# MCH_FPGA_Bank_0_CFG.net
KiCad netlist of a schematic drawn in Altium Designer
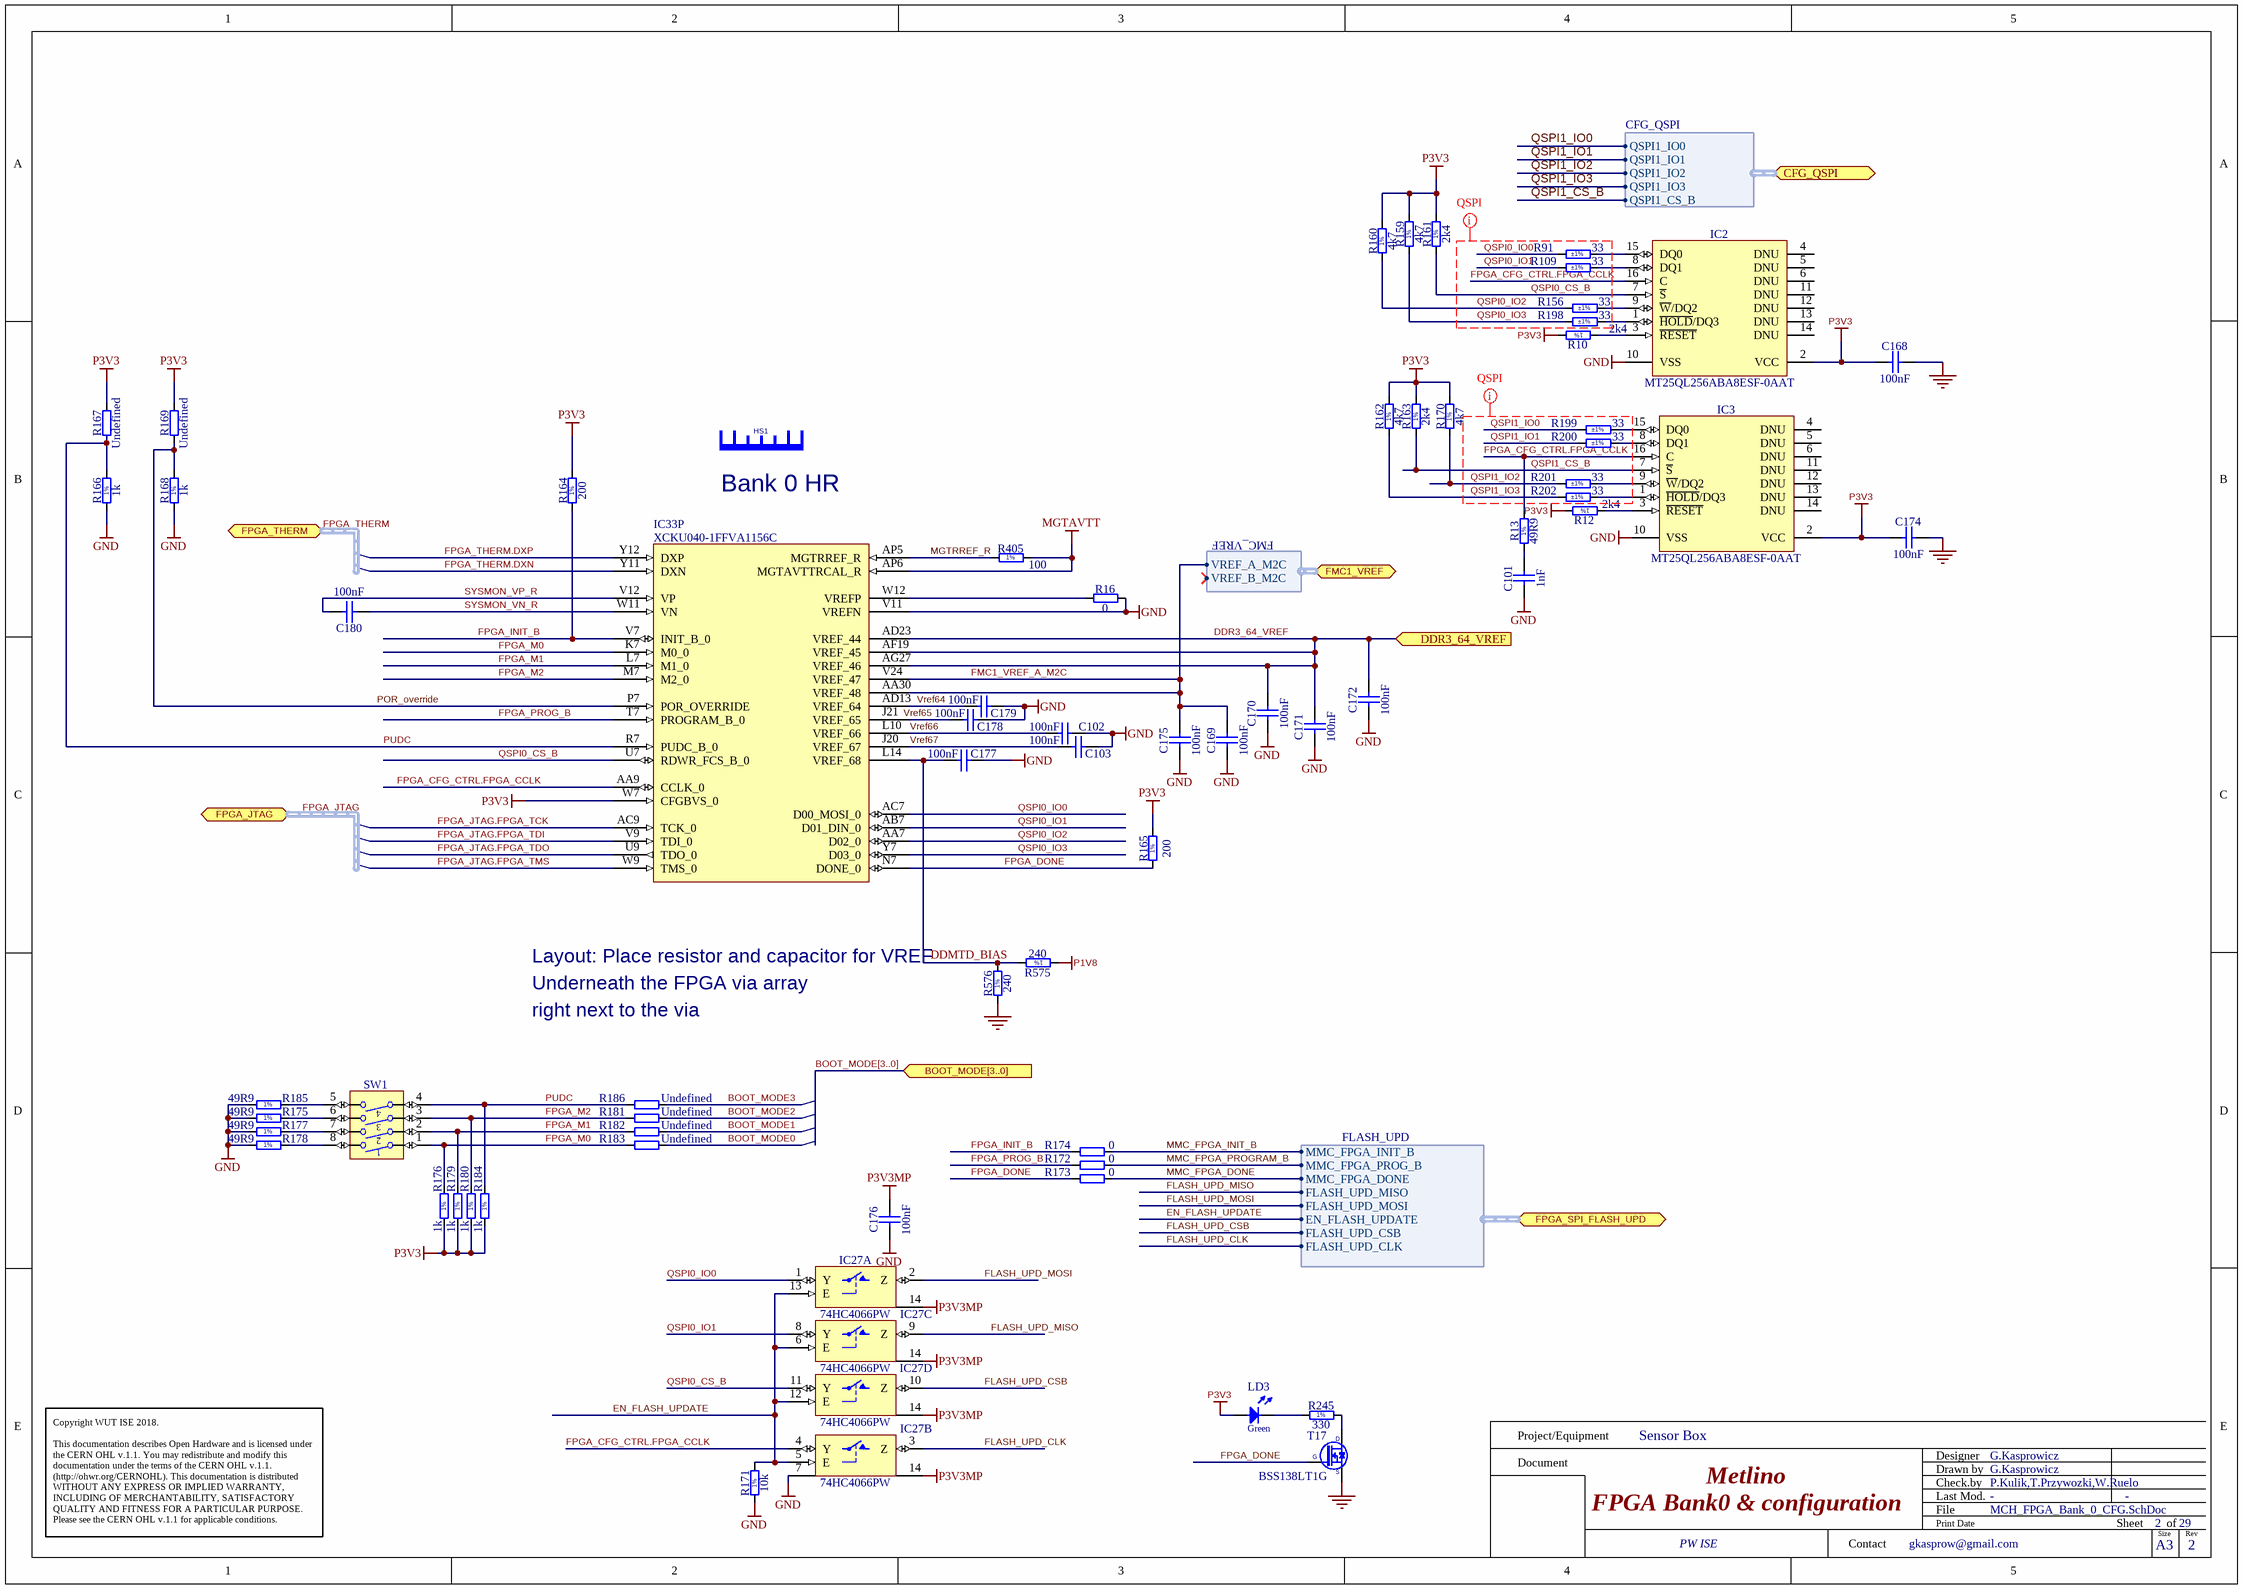
[diagram p0: MCH_FPGA_Bank_0_CFG.SchDoc]

(export (version "E")
  (design (tool "Eeschema 10.0.6"))
  (components
    (comp (ref "C101")
      (value "1nF")
      (footprint "CAPC1005X55N")
      (description "Non-polarised capacitor")
      (fields
        (field (name "MANUFACTURER PART NUMBER") "CC0402_1NF_50V_10%_X7R")
        (field (name "MANUFACTURER") "GENERIC")
        (field (name "AUTHOR") "CERN DEM JLC")
      )
      (libsource (lib "Capacitors") (part "Capacitor - non polarized"))
    )
    (comp (ref "C102")
      (value "100nF")
      (footprint "CAPC0603X33N")
      (description "Non-polarised capacitor")
      (fields
        (field (name "MANUFACTURER PART NUMBER") "CC0201_100NF_6.3V_10%_X5R")
        (field (name "MANUFACTURER") "GENERIC")
        (field (name "AUTHOR") "CERN DEM JLC")
      )
      (libsource (lib "Capacitors") (part "Capacitor - non polarized"))
    )
    (comp (ref "C103")
      (value "100nF")
      (footprint "CAPC0603X33N")
      (description "Non-polarised capacitor")
      (fields
        (field (name "MANUFACTURER PART NUMBER") "CC0201_100NF_6.3V_10%_X5R")
        (field (name "MANUFACTURER") "GENERIC")
        (field (name "AUTHOR") "CERN DEM JLC")
      )
      (libsource (lib "Capacitors") (part "Capacitor - non polarized"))
    )
    (comp (ref "C168")
      (value "100nF")
      (footprint "CAPC0603X33N")
      (description "Non-polarised capacitor")
      (fields
        (field (name "MANUFACTURER PART NUMBER") "CC0201_100NF_6.3V_10%_X5R")
        (field (name "MANUFACTURER") "GENERIC")
        (field (name "AUTHOR") "CERN DEM JLC")
      )
      (libsource (lib "Capacitors") (part "Capacitor - non polarized"))
    )
    (comp (ref "C169")
      (value "100nF")
      (footprint "CAPC0603X33N")
      (description "Non-polarised capacitor")
      (fields
        (field (name "MANUFACTURER PART NUMBER") "CC0201_100NF_6.3V_10%_X5R")
        (field (name "MANUFACTURER") "GENERIC")
        (field (name "AUTHOR") "CERN DEM JLC")
      )
      (libsource (lib "Capacitors") (part "Capacitor - non polarized"))
    )
    (comp (ref "C170")
      (value "100nF")
      (footprint "CAPC0603X33N")
      (description "Non-polarised capacitor")
      (fields
        (field (name "MANUFACTURER PART NUMBER") "CC0201_100NF_6.3V_10%_X5R")
        (field (name "MANUFACTURER") "GENERIC")
        (field (name "AUTHOR") "CERN DEM JLC")
      )
      (libsource (lib "Capacitors") (part "Capacitor - non polarized"))
    )
    (comp (ref "C171")
      (value "100nF")
      (footprint "CAPC0603X33N")
      (description "Non-polarised capacitor")
      (fields
        (field (name "MANUFACTURER PART NUMBER") "CC0201_100NF_6.3V_10%_X5R")
        (field (name "MANUFACTURER") "GENERIC")
        (field (name "AUTHOR") "CERN DEM JLC")
      )
      (libsource (lib "Capacitors") (part "Capacitor - non polarized"))
    )
    (comp (ref "C172")
      (value "100nF")
      (footprint "CAPC0603X33N")
      (description "Non-polarised capacitor")
      (fields
        (field (name "MANUFACTURER PART NUMBER") "CC0201_100NF_6.3V_10%_X5R")
        (field (name "MANUFACTURER") "GENERIC")
        (field (name "AUTHOR") "CERN DEM JLC")
      )
      (libsource (lib "Capacitors") (part "Capacitor - non polarized"))
    )
    (comp (ref "C174")
      (value "100nF")
      (footprint "CAPC0603X33N")
      (description "Non-polarised capacitor")
      (fields
        (field (name "MANUFACTURER PART NUMBER") "CC0201_100NF_6.3V_10%_X5R")
        (field (name "MANUFACTURER") "GENERIC")
        (field (name "AUTHOR") "CERN DEM JLC")
      )
      (libsource (lib "Capacitors") (part "Capacitor - non polarized"))
    )
    (comp (ref "C175")
      (value "100nF")
      (footprint "CAPC0603X33N")
      (description "Non-polarised capacitor")
      (fields
        (field (name "MANUFACTURER PART NUMBER") "CC0201_100NF_6.3V_10%_X5R")
        (field (name "MANUFACTURER") "GENERIC")
        (field (name "AUTHOR") "CERN DEM JLC")
      )
      (libsource (lib "Capacitors") (part "Capacitor - non polarized"))
    )
    (comp (ref "C176")
      (value "100nF")
      (footprint "CAPC0603X33N")
      (description "Non-polarised capacitor")
      (fields
        (field (name "MANUFACTURER PART NUMBER") "CC0201_100NF_6.3V_10%_X5R")
        (field (name "MANUFACTURER") "GENERIC")
        (field (name "AUTHOR") "CERN DEM JLC")
      )
      (libsource (lib "Capacitors") (part "Capacitor - non polarized"))
    )
    (comp (ref "C177")
      (value "100nF")
      (footprint "CAPC0603X33N")
      (description "Non-polarised capacitor")
      (fields
        (field (name "MANUFACTURER PART NUMBER") "CC0201_100NF_6.3V_10%_X5R")
        (field (name "MANUFACTURER") "GENERIC")
        (field (name "AUTHOR") "CERN DEM JLC")
      )
      (libsource (lib "Capacitors") (part "Capacitor - non polarized"))
    )
    (comp (ref "C178")
      (value "100nF")
      (footprint "CAPC0603X33N")
      (description "Non-polarised capacitor")
      (fields
        (field (name "MANUFACTURER PART NUMBER") "CC0201_100NF_6.3V_10%_X5R")
        (field (name "MANUFACTURER") "GENERIC")
        (field (name "AUTHOR") "CERN DEM JLC")
      )
      (libsource (lib "Capacitors") (part "Capacitor - non polarized"))
    )
    (comp (ref "C179")
      (value "100nF")
      (footprint "CAPC0603X33N")
      (description "Non-polarised capacitor")
      (fields
        (field (name "MANUFACTURER PART NUMBER") "CC0201_100NF_6.3V_10%_X5R")
        (field (name "MANUFACTURER") "GENERIC")
        (field (name "AUTHOR") "CERN DEM JLC")
      )
      (libsource (lib "Capacitors") (part "Capacitor - non polarized"))
    )
    (comp (ref "C180")
      (value "100nF")
      (footprint "CAPC0603X33N")
      (description "Non-polarised capacitor")
      (fields
        (field (name "MANUFACTURER PART NUMBER") "CC0201_100NF_6.3V_10%_X5R")
        (field (name "MANUFACTURER") "GENERIC")
        (field (name "AUTHOR") "CERN DEM JLC")
      )
      (libsource (lib "Capacitors") (part "Capacitor - non polarized"))
    )
    (comp (ref "HS1")
      (value "Heat Sink No Pad")
      (footprint "HSINK_WAKEFIELD_SKV585811-CU")
      (description "Heat Sink Without Pad")
      (fields
        (field (name "PART NUMBER") "HSINK_WAKEFIELD_SKV585811-CU")
        (field (name "MANUFACTURER") "WAKEFIELD-VETTE")
        (field (name "AUTHOR") "CERN DEM JMW")
      )
      (libsource (lib "Eletro-mechanical") (part "Heat Sink No Pad"))
    )
    (comp (ref "IC2")
      (value "MT25QL256ABA8ESF-0AAT")
      (footprint "SOIC127P1030X265-16N")
      (description "256Mbit (32MB), 2.7V-3.6V, Multiple I/O Serial NOR Flash Memory,with Reset# & Hold#")
      (fields (field (name "MANUFACTURER") "MICRON TECHNOLOGY") (field (name "AUTHOR") "CERN DEM JLC"))
      (libsource (lib "ICs And Semiconductors") (part "MT25QL256ABA8ESF"))
    )
    (comp (ref "IC3")
      (value "MT25QL256ABA8ESF-0AAT")
      (footprint "SOIC127P1030X265-16N")
      (description "256Mbit (32MB), 2.7V-3.6V, Multiple I/O Serial NOR Flash Memory,with Reset# & Hold#")
      (fields (field (name "MANUFACTURER") "MICRON TECHNOLOGY") (field (name "AUTHOR") "CERN DEM JLC"))
      (libsource (lib "ICs And Semiconductors") (part "MT25QL256ABA8ESF"))
    )
    (comp (ref "IC27")
      (value "74HC4066PW")
      (footprint "SOP65P640X110-14N")
      (fields (field (name "MANUFACTURER") "NXP SEMICONDUCTORS") (field (name "AUTHOR") "CERN DEM JLC"))
      (libsource (lib "ICs And Semiconductors") (part "4066"))
    )
    (comp (ref "IC33")
      (value "XCKU040-1FFVA1156C")
      (footprint "BGA1156C100P34X34_3500X3500X350")
      (description "Kintex UltraScale FPGA, 520 I/O, 530K Cells, 1156-Ball BGA, Speed Grade 1, Commercial Grade")
      (fields (field (name "MANUFACTURER") "XILINX") (field (name "AUTHOR") "CERN DEM CA"))
      (libsource (lib "ICs And Semiconductors") (part "XCKU040-1FFVA1156C"))
    )
    (comp (ref "LD3")
      (value "Green")
      (footprint "LED_AVAGO_HSME-C120")
      (description "LED Green 1C 2A")
      (fields
        (field (name "MANUFACTURER PART NUMBER") "HSME-C120")
        (field (name "MANUFACTURER") "AVAGO TECHNOLOGIES")
        (field (name "AUTHOR") "CERN DEM JMW")
      )
      (libsource (lib "ICs And Semiconductors") (part "LED Green 1C 2A"))
    )
    (comp (ref "R10")
      (value "2k4")
      (footprint "RESC1005X40N")
      (description "Resistor - 1%")
      (fields
        (field (name "MANUFACTURER PART NUMBER") "R0402_2K4_1%_0.0625W_100PPM")
        (field (name "MANUFACTURER") "GENERIC")
        (field (name "AUTHOR") "CERN DEM JLC")
      )
      (libsource (lib "Resistors") (part "Resistor - 1%"))
    )
    (comp (ref "R12")
      (value "2k4")
      (footprint "RESC1005X40N")
      (description "Resistor - 1%")
      (fields
        (field (name "MANUFACTURER PART NUMBER") "R0402_2K4_1%_0.0625W_100PPM")
        (field (name "MANUFACTURER") "GENERIC")
        (field (name "AUTHOR") "CERN DEM JLC")
      )
      (libsource (lib "Resistors") (part "Resistor - 1%"))
    )
    (comp (ref "R13")
      (value "49R9")
      (footprint "RESC1005X40N")
      (description "Resistor - 1%")
      (fields
        (field (name "MANUFACTURER PART NUMBER") "R0402_49R9_1%_0.0625W_100PPM")
        (field (name "MANUFACTURER") "GENERIC")
        (field (name "AUTHOR") "CERN DEM JLC")
      )
      (libsource (lib "Resistors") (part "Resistor - 1%"))
    )
    (comp (ref "R16")
      (value "0")
      (footprint "RESC1005X40N")
      (description "Resistor")
      (fields
        (field (name "MANUFACTURER PART NUMBER") "R0402_0R_JUMPER")
        (field (name "MANUFACTURER") "GENERIC")
        (field (name "AUTHOR") "CERN DEM JLC")
      )
      (libsource (lib "Resistors") (part "Resistor"))
    )
    (comp (ref "R91")
      (value "33")
      (footprint "RESC1005X40N")
      (description "Resistor - 1%")
      (fields
        (field (name "TOLERANCE") "±1%")
        (field (name "PART NUMBER") "R0402_33R_1%_0.0625W_100PPM")
        (field (name "POWER") "0.0625W")
        (field (name "AUTHOR") "CERN DEM JLC")
      )
      (libsource (lib "Resistors") (part "Resistor - 1%"))
    )
    (comp (ref "R109")
      (value "33")
      (footprint "RESC1005X40N")
      (description "Resistor - 1%")
      (fields
        (field (name "TOLERANCE") "±1%")
        (field (name "PART NUMBER") "R0402_33R_1%_0.0625W_100PPM")
        (field (name "POWER") "0.0625W")
        (field (name "AUTHOR") "CERN DEM JLC")
      )
      (libsource (lib "Resistors") (part "Resistor - 1%"))
    )
    (comp (ref "R156")
      (value "33")
      (footprint "RESC1005X40N")
      (description "Resistor - 1%")
      (fields
        (field (name "TOLERANCE") "±1%")
        (field (name "PART NUMBER") "R0402_33R_1%_0.0625W_100PPM")
        (field (name "POWER") "0.0625W")
        (field (name "AUTHOR") "CERN DEM JLC")
      )
      (libsource (lib "Resistors") (part "Resistor - 1%"))
    )
    (comp (ref "R159")
      (value "4k7")
      (footprint "RESC1005X40N")
      (description "Resistor - 1%")
      (fields
        (field (name "MANUFACTURER PART NUMBER") "R0402_4K7_1%_0.0625W_100PPM")
        (field (name "MANUFACTURER") "GENERIC")
        (field (name "AUTHOR") "CERN DEM JLC")
      )
      (libsource (lib "Resistors") (part "Resistor - 1%"))
    )
    (comp (ref "R160")
      (value "4k7")
      (footprint "RESC1005X40N")
      (description "Resistor - 1%")
      (fields
        (field (name "MANUFACTURER PART NUMBER") "R0402_4K7_1%_0.0625W_100PPM")
        (field (name "MANUFACTURER") "GENERIC")
        (field (name "AUTHOR") "CERN DEM JLC")
      )
      (libsource (lib "Resistors") (part "Resistor - 1%"))
    )
    (comp (ref "R161")
      (value "2k4")
      (footprint "RESC1005X40N")
      (description "Resistor - 1%")
      (fields
        (field (name "MANUFACTURER PART NUMBER") "R0402_2K4_1%_0.0625W_100PPM")
        (field (name "MANUFACTURER") "GENERIC")
        (field (name "AUTHOR") "CERN DEM JLC")
      )
      (libsource (lib "Resistors") (part "Resistor - 1%"))
    )
    (comp (ref "R162")
      (value "4k7")
      (footprint "RESC1005X40N")
      (description "Resistor - 1%")
      (fields
        (field (name "MANUFACTURER PART NUMBER") "R0402_4K7_1%_0.0625W_100PPM")
        (field (name "MANUFACTURER") "GENERIC")
        (field (name "AUTHOR") "CERN DEM JLC")
      )
      (libsource (lib "Resistors") (part "Resistor - 1%"))
    )
    (comp (ref "R163")
      (value "2k4")
      (footprint "RESC1005X40N")
      (description "Resistor - 1%")
      (fields
        (field (name "MANUFACTURER PART NUMBER") "R0402_2K4_1%_0.0625W_100PPM")
        (field (name "MANUFACTURER") "GENERIC")
        (field (name "AUTHOR") "CERN DEM JLC")
      )
      (libsource (lib "Resistors") (part "Resistor - 1%"))
    )
    (comp (ref "R164")
      (value "200")
      (footprint "RESC1005X40N")
      (description "Resistor - 1%")
      (fields
        (field (name "MANUFACTURER PART NUMBER") "R0402_200R_1%_0.0625W_100PPM")
        (field (name "MANUFACTURER") "GENERIC")
        (field (name "AUTHOR") "CERN DEM JLC")
      )
      (libsource (lib "Resistors") (part "Resistor - 1%"))
    )
    (comp (ref "R165")
      (value "200")
      (footprint "RESC1005X40N")
      (description "Resistor - 1%")
      (fields
        (field (name "MANUFACTURER PART NUMBER") "R0402_200R_1%_0.0625W_100PPM")
        (field (name "MANUFACTURER") "GENERIC")
        (field (name "AUTHOR") "CERN DEM JLC")
      )
      (libsource (lib "Resistors") (part "Resistor - 1%"))
    )
    (comp (ref "R166")
      (value "1k")
      (footprint "RESC1005X40N")
      (description "Resistor - 1%")
      (fields
        (field (name "MANUFACTURER PART NUMBER") "R0402_1K_1%_0.0625W_100PPM")
        (field (name "MANUFACTURER") "GENERIC")
        (field (name "AUTHOR") "CERN DEM JLC")
      )
      (libsource (lib "Resistors") (part "Resistor - 1%"))
    )
    (comp (ref "R167")
      (value "Undefined")
      (footprint "RESC1005X40N")
      (description "Resistor")
      (fields
        (field (name "MANUFACTURER PART NUMBER") "R0402_NO-VALUE")
        (field (name "AUTHOR") "CERN DEM JLC")
      )
      (libsource (lib "Resistors") (part "Resistor"))
    )
    (comp (ref "R168")
      (value "1k")
      (footprint "RESC1005X40N")
      (description "Resistor - 1%")
      (fields
        (field (name "MANUFACTURER PART NUMBER") "R0402_1K_1%_0.0625W_100PPM")
        (field (name "MANUFACTURER") "GENERIC")
        (field (name "AUTHOR") "CERN DEM JLC")
      )
      (libsource (lib "Resistors") (part "Resistor - 1%"))
    )
    (comp (ref "R169")
      (value "Undefined")
      (footprint "RESC1005X40N")
      (description "Resistor")
      (fields
        (field (name "MANUFACTURER PART NUMBER") "R0402_NO-VALUE")
        (field (name "AUTHOR") "CERN DEM JLC")
      )
      (libsource (lib "Resistors") (part "Resistor"))
    )
    (comp (ref "R170")
      (value "4k7")
      (footprint "RESC1005X40N")
      (description "Resistor - 1%")
      (fields
        (field (name "MANUFACTURER PART NUMBER") "R0402_4K7_1%_0.0625W_100PPM")
        (field (name "MANUFACTURER") "GENERIC")
        (field (name "AUTHOR") "CERN DEM JLC")
      )
      (libsource (lib "Resistors") (part "Resistor - 1%"))
    )
    (comp (ref "R171")
      (value "10k")
      (footprint "RESC1005X40N")
      (description "Resistor - 1%")
      (fields
        (field (name "MANUFACTURER PART NUMBER") "R0402_10K_1%_0.0625W_100PPM")
        (field (name "MANUFACTURER") "GENERIC")
        (field (name "AUTHOR") "CERN DEM JLC")
      )
      (libsource (lib "Resistors") (part "Resistor - 1%"))
    )
    (comp (ref "R172")
      (value "0")
      (footprint "RESC1005X40N")
      (description "Resistor")
      (fields
        (field (name "MANUFACTURER PART NUMBER") "R0402_0R_JUMPER")
        (field (name "MANUFACTURER") "GENERIC")
        (field (name "AUTHOR") "CERN DEM JLC")
      )
      (libsource (lib "Resistors") (part "Resistor"))
    )
    (comp (ref "R173")
      (value "0")
      (footprint "RESC1005X40N")
      (description "Resistor")
      (fields
        (field (name "MANUFACTURER PART NUMBER") "R0402_0R_JUMPER")
        (field (name "MANUFACTURER") "GENERIC")
        (field (name "AUTHOR") "CERN DEM JLC")
      )
      (libsource (lib "Resistors") (part "Resistor"))
    )
    (comp (ref "R174")
      (value "0")
      (footprint "RESC1005X40N")
      (description "Resistor")
      (fields
        (field (name "MANUFACTURER PART NUMBER") "R0402_0R_JUMPER")
        (field (name "MANUFACTURER") "GENERIC")
        (field (name "AUTHOR") "CERN DEM JLC")
      )
      (libsource (lib "Resistors") (part "Resistor"))
    )
    (comp (ref "R175")
      (value "49R9")
      (footprint "RESC1005X40N")
      (description "Resistor - 1%")
      (fields
        (field (name "MANUFACTURER PART NUMBER") "R0402_49R9_1%_0.0625W_100PPM")
        (field (name "MANUFACTURER") "GENERIC")
        (field (name "AUTHOR") "CERN DEM JLC")
      )
      (libsource (lib "Resistors") (part "Resistor - 1%"))
    )
    (comp (ref "R176")
      (value "1k")
      (footprint "RESC1005X40N")
      (description "Resistor - 1%")
      (fields
        (field (name "MANUFACTURER PART NUMBER") "R0402_1K_1%_0.0625W_100PPM")
        (field (name "MANUFACTURER") "GENERIC")
        (field (name "AUTHOR") "CERN DEM JLC")
      )
      (libsource (lib "Resistors") (part "Resistor - 1%"))
    )
    (comp (ref "R177")
      (value "49R9")
      (footprint "RESC1005X40N")
      (description "Resistor - 1%")
      (fields
        (field (name "MANUFACTURER PART NUMBER") "R0402_49R9_1%_0.0625W_100PPM")
        (field (name "MANUFACTURER") "GENERIC")
        (field (name "AUTHOR") "CERN DEM JLC")
      )
      (libsource (lib "Resistors") (part "Resistor - 1%"))
    )
    (comp (ref "R178")
      (value "49R9")
      (footprint "RESC1005X40N")
      (description "Resistor - 1%")
      (fields
        (field (name "MANUFACTURER PART NUMBER") "R0402_49R9_1%_0.0625W_100PPM")
        (field (name "MANUFACTURER") "GENERIC")
        (field (name "AUTHOR") "CERN DEM JLC")
      )
      (libsource (lib "Resistors") (part "Resistor - 1%"))
    )
    (comp (ref "R179")
      (value "1k")
      (footprint "RESC1005X40N")
      (description "Resistor - 1%")
      (fields
        (field (name "MANUFACTURER PART NUMBER") "R0402_1K_1%_0.0625W_100PPM")
        (field (name "MANUFACTURER") "GENERIC")
        (field (name "AUTHOR") "CERN DEM JLC")
      )
      (libsource (lib "Resistors") (part "Resistor - 1%"))
    )
    (comp (ref "R180")
      (value "1k")
      (footprint "RESC1005X40N")
      (description "Resistor - 1%")
      (fields
        (field (name "MANUFACTURER PART NUMBER") "R0402_1K_1%_0.0625W_100PPM")
        (field (name "MANUFACTURER") "GENERIC")
        (field (name "AUTHOR") "CERN DEM JLC")
      )
      (libsource (lib "Resistors") (part "Resistor - 1%"))
    )
    (comp (ref "R181")
      (value "Undefined")
      (footprint "RESC1005X40N")
      (description "Resistor")
      (fields
        (field (name "MANUFACTURER PART NUMBER") "R0402_NO-VALUE")
        (field (name "AUTHOR") "CERN DEM JLC")
      )
      (libsource (lib "Resistors") (part "Resistor"))
    )
    (comp (ref "R182")
      (value "Undefined")
      (footprint "RESC1005X40N")
      (description "Resistor")
      (fields
        (field (name "MANUFACTURER PART NUMBER") "R0402_NO-VALUE")
        (field (name "AUTHOR") "CERN DEM JLC")
      )
      (libsource (lib "Resistors") (part "Resistor"))
    )
    (comp (ref "R183")
      (value "Undefined")
      (footprint "RESC1005X40N")
      (description "Resistor")
      (fields
        (field (name "MANUFACTURER PART NUMBER") "R0402_NO-VALUE")
        (field (name "AUTHOR") "CERN DEM JLC")
      )
      (libsource (lib "Resistors") (part "Resistor"))
    )
    (comp (ref "R184")
      (value "1k")
      (footprint "RESC1005X40N")
      (description "Resistor - 1%")
      (fields
        (field (name "MANUFACTURER PART NUMBER") "R0402_1K_1%_0.0625W_100PPM")
        (field (name "MANUFACTURER") "GENERIC")
        (field (name "AUTHOR") "CERN DEM JLC")
      )
      (libsource (lib "Resistors") (part "Resistor - 1%"))
    )
    (comp (ref "R185")
      (value "49R9")
      (footprint "RESC1005X40N")
      (description "Resistor - 1%")
      (fields
        (field (name "MANUFACTURER PART NUMBER") "R0402_49R9_1%_0.0625W_100PPM")
        (field (name "MANUFACTURER") "GENERIC")
        (field (name "AUTHOR") "CERN DEM JLC")
      )
      (libsource (lib "Resistors") (part "Resistor - 1%"))
    )
    (comp (ref "R186")
      (value "Undefined")
      (footprint "RESC1005X40N")
      (description "Resistor")
      (fields
        (field (name "MANUFACTURER PART NUMBER") "R0402_NO-VALUE")
        (field (name "AUTHOR") "CERN DEM JLC")
      )
      (libsource (lib "Resistors") (part "Resistor"))
    )
    (comp (ref "R198")
      (value "33")
      (footprint "RESC1005X40N")
      (description "Resistor - 1%")
      (fields
        (field (name "TOLERANCE") "±1%")
        (field (name "PART NUMBER") "R0402_33R_1%_0.0625W_100PPM")
        (field (name "POWER") "0.0625W")
        (field (name "AUTHOR") "CERN DEM JLC")
      )
      (libsource (lib "Resistors") (part "Resistor - 1%"))
    )
    (comp (ref "R199")
      (value "33")
      (footprint "RESC1005X40N")
      (description "Resistor - 1%")
      (fields
        (field (name "TOLERANCE") "±1%")
        (field (name "PART NUMBER") "R0402_33R_1%_0.0625W_100PPM")
        (field (name "POWER") "0.0625W")
        (field (name "AUTHOR") "CERN DEM JLC")
      )
      (libsource (lib "Resistors") (part "Resistor - 1%"))
    )
    (comp (ref "R200")
      (value "33")
      (footprint "RESC1005X40N")
      (description "Resistor - 1%")
      (fields
        (field (name "TOLERANCE") "±1%")
        (field (name "PART NUMBER") "R0402_33R_1%_0.0625W_100PPM")
        (field (name "POWER") "0.0625W")
        (field (name "AUTHOR") "CERN DEM JLC")
      )
      (libsource (lib "Resistors") (part "Resistor - 1%"))
    )
    (comp (ref "R201")
      (value "33")
      (footprint "RESC1005X40N")
      (description "Resistor - 1%")
      (fields
        (field (name "TOLERANCE") "±1%")
        (field (name "PART NUMBER") "R0402_33R_1%_0.0625W_100PPM")
        (field (name "POWER") "0.0625W")
        (field (name "AUTHOR") "CERN DEM JLC")
      )
      (libsource (lib "Resistors") (part "Resistor - 1%"))
    )
    (comp (ref "R202")
      (value "33")
      (footprint "RESC1005X40N")
      (description "Resistor - 1%")
      (fields
        (field (name "TOLERANCE") "±1%")
        (field (name "PART NUMBER") "R0402_33R_1%_0.0625W_100PPM")
        (field (name "POWER") "0.0625W")
        (field (name "AUTHOR") "CERN DEM JLC")
      )
      (libsource (lib "Resistors") (part "Resistor - 1%"))
    )
    (comp (ref "R245")
      (value "330")
      (footprint "RESC1005X40N")
      (description "Resistor - 1%")
      (fields
        (field (name "MANUFACTURER PART NUMBER") "R0402_330R_1%_0.0625W_100PPM")
        (field (name "MANUFACTURER") "GENERIC")
        (field (name "AUTHOR") "CERN DEM JLC")
      )
      (libsource (lib "Resistors") (part "Resistor - 1%"))
    )
    (comp (ref "R405")
      (value "100")
      (footprint "RESC0603X28N")
      (description "Resistor - 1%")
      (fields
        (field (name "MANUFACTURER PART NUMBER") "R0201_100R_1%_0.05W_200PPM")
        (field (name "MANUFACTURER") "GENERIC")
        (field (name "AUTHOR") "CERN DEM JLC")
      )
      (libsource (lib "Resistors") (part "Resistor - 1%"))
    )
    (comp (ref "R575")
      (value "240")
      (footprint "RESC1005X40N")
      (description "Resistor - 1%")
      (fields
        (field (name "MANUFACTURER PART NUMBER") "R0402_240R_1%_0.0625W_100PPM")
        (field (name "MANUFACTURER") "GENERIC")
        (field (name "AUTHOR") "CERN DEM JLC")
      )
      (libsource (lib "Resistors") (part "Resistor - 1%"))
    )
    (comp (ref "R576")
      (value "240")
      (footprint "RESC1005X40N")
      (description "Resistor - 1%")
      (fields
        (field (name "MANUFACTURER PART NUMBER") "R0402_240R_1%_0.0625W_100PPM")
        (field (name "MANUFACTURER") "GENERIC")
        (field (name "AUTHOR") "CERN DEM JLC")
      )
      (libsource (lib "Resistors") (part "Resistor - 1%"))
    )
    (comp (ref "SW1")
      (value "Switch")
      (footprint "SW_TYCO_1571983-4")
      (description "4 Ways SPST DIP Switch")
      (fields
        (field (name "MANUFACTURER PART NUMBER") "1571983-4 or GDH04S04")
        (field (name "MANUFACTURER") "TYCO")
        (field (name "AUTHOR") "CERN DEM JLC")
      )
      (libsource (lib "Eletro-mechanical") (part "SW 4x SPST DIP Switch"))
    )
    (comp (ref "T17")
      (value "BSS138LT1G")
      (footprint "SOT95P240X110-3N")
      (description "N-CHANNEL MOSFET WITH DIODE")
      (fields (field (name "MANUFACTURER") "ON SEMICONDUCTOR") (field (name "AUTHOR") "CERN DEM JLC"))
      (libsource (lib "ICs And Semiconductors") (part "N-MOSFET-D 1G 2S 3D"))
    )
  )
  (nets
    (net (code "6") (name "/BOOT_MODE0") (class "Default")
      (node (ref "R183") (pin "2") (pinfunction "2_2") (pintype "passive"))
    )
    (net (code "7") (name "/BOOT_MODE1") (class "Default")
      (node (ref "R182") (pin "2") (pinfunction "2_2") (pintype "passive"))
    )
    (net (code "8") (name "/BOOT_MODE2") (class "Default")
      (node (ref "R181") (pin "2") (pinfunction "2_2") (pintype "passive"))
    )
    (net (code "9") (name "/BOOT_MODE3") (class "Default")
      (node (ref "R186") (pin "2") (pinfunction "2_2") (pintype "passive"))
    )
    (net (code "11") (name "/DDMTD_BIAS") (class "Default")
      (node (ref "C177") (pin "1") (pinfunction "1_1") (pintype "passive"))
      (node (ref "IC33") (pin "L14") (pinfunction "VREF_68_L14") (pintype "power_in"))
      (node (ref "R575") (pin "2") (pinfunction "2_2") (pintype "passive"))
      (node (ref "R576") (pin "2") (pinfunction "2_2") (pintype "passive"))
    )
    (net (code "12") (name "/DDR3_64_VREF") (class "Default")
      (node (ref "C170") (pin "1") (pinfunction "1_1") (pintype "passive"))
      (node (ref "C171") (pin "1") (pinfunction "1_1") (pintype "passive"))
      (node (ref "C172") (pin "1") (pinfunction "1_1") (pintype "passive"))
      (node (ref "IC33") (pin "AD23") (pinfunction "VREF_44_AD23") (pintype "power_in"))
      (node (ref "IC33") (pin "AF19") (pinfunction "VREF_45_AF19") (pintype "power_in"))
      (node (ref "IC33") (pin "AG27") (pinfunction "VREF_46_AG27") (pintype "power_in"))
    )
    (net (code "13") (name "/EN_FLASH_UPDATE") (class "Default")
      (node (ref "IC27") (pin "12") (pinfunction "E_12") (pintype "input"))
      (node (ref "IC27") (pin "13") (pinfunction "E_13") (pintype "input"))
      (node (ref "IC27") (pin "5") (pinfunction "E_5") (pintype "input"))
      (node (ref "IC27") (pin "6") (pinfunction "E_6") (pintype "input"))
      (node (ref "R171") (pin "2") (pinfunction "2_2") (pintype "passive"))
    )
    (net (code "14") (name "/FLASH_UPD_CLK") (class "Default")
      (node (ref "IC27") (pin "3") (pinfunction "Z_3") (pintype "bidirectional"))
    )
    (net (code "15") (name "/FLASH_UPD_CSB") (class "Default")
      (node (ref "IC27") (pin "10") (pinfunction "Z_10") (pintype "bidirectional"))
    )
    (net (code "16") (name "/FLASH_UPD_MISO") (class "Default")
      (node (ref "IC27") (pin "9") (pinfunction "Z_9") (pintype "bidirectional"))
    )
    (net (code "17") (name "/FLASH_UPD_MOSI") (class "Default")
      (node (ref "IC27") (pin "2") (pinfunction "Z_2") (pintype "bidirectional"))
    )
    (net (code "18") (name "/FMC1_VREF_A_M2C") (class "Default")
      (node (ref "C169") (pin "1") (pinfunction "1_1") (pintype "passive"))
      (node (ref "C175") (pin "1") (pinfunction "1_1") (pintype "passive"))
      (node (ref "IC33") (pin "AA30") (pinfunction "VREF_48_AA30") (pintype "power_in"))
      (node (ref "IC33") (pin "V24") (pinfunction "VREF_47_V24") (pintype "power_in"))
    )
    (net (code "19") (name "/FPGA_CFG_CTRL.FPGA_CCLK") (class "Default")
      (node (ref "IC2") (pin "16") (pinfunction "C_16") (pintype "input"))
      (node (ref "IC27") (pin "4") (pinfunction "Y_4") (pintype "bidirectional"))
      (node (ref "IC3") (pin "16") (pinfunction "C_16") (pintype "input"))
      (node (ref "IC33") (pin "AA9") (pinfunction "CCLK_0_AA9") (pintype "bidirectional"))
      (node (ref "R13") (pin "2") (pinfunction "2_2") (pintype "passive"))
    )
    (net (code "20") (name "/FPGA_DONE") (class "Default")
      (node (ref "IC33") (pin "N7") (pinfunction "DONE_0_N7") (pintype "bidirectional"))
      (node (ref "R165") (pin "1") (pinfunction "1_1") (pintype "passive"))
      (node (ref "R173") (pin "1") (pinfunction "1_1") (pintype "passive"))
      (node (ref "T17") (pin "1") (pinfunction "G_1") (pintype "passive"))
    )
    (net (code "21") (name "/FPGA_INIT_B") (class "Default")
      (node (ref "IC33") (pin "V7") (pinfunction "INIT_B_0_V7") (pintype "bidirectional"))
      (node (ref "R164") (pin "1") (pinfunction "1_1") (pintype "passive"))
      (node (ref "R174") (pin "1") (pinfunction "1_1") (pintype "passive"))
    )
    (net (code "22") (name "/FPGA_JTAG.FPGA_TCK") (class "Default")
      (node (ref "IC33") (pin "AC9") (pinfunction "TCK_0_AC9") (pintype "input"))
    )
    (net (code "23") (name "/FPGA_JTAG.FPGA_TDI") (class "Default")
      (node (ref "IC33") (pin "V9") (pinfunction "TDI_0_V9") (pintype "input"))
    )
    (net (code "24") (name "/FPGA_JTAG.FPGA_TDO") (class "Default")
      (node (ref "IC33") (pin "U9") (pinfunction "TDO_0_U9") (pintype "output"))
    )
    (net (code "25") (name "/FPGA_JTAG.FPGA_TMS") (class "Default")
      (node (ref "IC33") (pin "W9") (pinfunction "TMS_0_W9") (pintype "input"))
    )
    (net (code "26") (name "/FPGA_M0") (class "Default")
      (node (ref "IC33") (pin "K7") (pinfunction "M0_0_K7") (pintype "input"))
      (node (ref "R176") (pin "2") (pinfunction "2_2") (pintype "passive"))
      (node (ref "R183") (pin "1") (pinfunction "1_1") (pintype "passive"))
      (node (ref "SW1") (pin "1") (pinfunction "1_1") (pintype "bidirectional"))
    )
    (net (code "27") (name "/FPGA_M1") (class "Default")
      (node (ref "IC33") (pin "L7") (pinfunction "M1_0_L7") (pintype "input"))
      (node (ref "R179") (pin "2") (pinfunction "2_2") (pintype "passive"))
      (node (ref "R182") (pin "1") (pinfunction "1_1") (pintype "passive"))
      (node (ref "SW1") (pin "2") (pinfunction "2_2") (pintype "bidirectional"))
    )
    (net (code "28") (name "/FPGA_M2") (class "Default")
      (node (ref "IC33") (pin "M7") (pinfunction "M2_0_M7") (pintype "input"))
      (node (ref "R180") (pin "2") (pinfunction "2_2") (pintype "passive"))
      (node (ref "R181") (pin "1") (pinfunction "1_1") (pintype "passive"))
      (node (ref "SW1") (pin "3") (pinfunction "3_3") (pintype "bidirectional"))
    )
    (net (code "29") (name "/FPGA_PROG_B") (class "Default")
      (node (ref "IC33") (pin "T7") (pinfunction "PROGRAM_B_0_T7") (pintype "input"))
      (node (ref "R172") (pin "1") (pinfunction "1_1") (pintype "passive"))
    )
    (net (code "30") (name "/FPGA_THERM.DXN") (class "Default")
      (node (ref "IC33") (pin "Y11") (pinfunction "DXN_Y11") (pintype "input"))
    )
    (net (code "31") (name "/FPGA_THERM.DXP") (class "Default")
      (node (ref "IC33") (pin "Y12") (pinfunction "DXP_Y12") (pintype "input"))
    )
    (net (code "32") (name "/MGTRREF_R") (class "Default")
      (node (ref "IC33") (pin "AP5") (pinfunction "MGTRREF_R_AP5") (pintype "input"))
      (node (ref "R405") (pin "1") (pinfunction "1_1") (pintype "passive"))
    )
    (net (code "33") (name "/MMC_FPGA_DONE") (class "Default")
      (node (ref "R173") (pin "2") (pinfunction "2_2") (pintype "passive"))
    )
    (net (code "34") (name "/MMC_FPGA_INIT_B") (class "Default")
      (node (ref "R174") (pin "2") (pinfunction "2_2") (pintype "passive"))
    )
    (net (code "35") (name "/MMC_FPGA_PROGRAM_B") (class "Default")
      (node (ref "R172") (pin "2") (pinfunction "2_2") (pintype "passive"))
    )
    (net (code "36") (name "/POR_override") (class "Default")
      (node (ref "IC33") (pin "P7") (pinfunction "POR_OVERRIDE_P7") (pintype "input"))
      (node (ref "R168") (pin "2") (pinfunction "2_2") (pintype "passive"))
      (node (ref "R169") (pin "1") (pinfunction "1_1") (pintype "passive"))
    )
    (net (code "37") (name "/PUDC") (class "Default")
      (node (ref "IC33") (pin "R7") (pinfunction "PUDC_B_0_R7") (pintype "input"))
      (node (ref "R166") (pin "2") (pinfunction "2_2") (pintype "passive"))
      (node (ref "R167") (pin "1") (pinfunction "1_1") (pintype "passive"))
      (node (ref "R184") (pin "2") (pinfunction "2_2") (pintype "passive"))
      (node (ref "R186") (pin "1") (pinfunction "1_1") (pintype "passive"))
      (node (ref "SW1") (pin "4") (pinfunction "4_4") (pintype "bidirectional"))
    )
    (net (code "38") (name "/QSPI0_CS_B") (class "Default")
      (node (ref "IC2") (pin "7") (pinfunction "~{S}_7") (pintype "input"))
      (node (ref "IC27") (pin "11") (pinfunction "Y_11") (pintype "bidirectional"))
      (node (ref "IC33") (pin "U7") (pinfunction "RDWR_FCS_B_0_U7") (pintype "bidirectional"))
      (node (ref "R161") (pin "1") (pinfunction "1_1") (pintype "passive"))
    )
    (net (code "39") (name "/QSPI0_IO0") (class "Default")
      (node (ref "IC27") (pin "1") (pinfunction "Y_1") (pintype "bidirectional"))
      (node (ref "IC33") (pin "AC7") (pinfunction "D00_MOSI_0_AC7") (pintype "bidirectional"))
      (node (ref "R91") (pin "1") (pinfunction "1_1") (pintype "passive"))
    )
    (net (code "40") (name "/QSPI0_IO1") (class "Default")
      (node (ref "IC27") (pin "8") (pinfunction "Y_8") (pintype "bidirectional"))
      (node (ref "IC33") (pin "AB7") (pinfunction "D01_DIN_0_AB7") (pintype "bidirectional"))
      (node (ref "R109") (pin "1") (pinfunction "1_1") (pintype "passive"))
    )
    (net (code "41") (name "/QSPI0_IO2") (class "Default")
      (node (ref "IC33") (pin "AA7") (pinfunction "D02_0_AA7") (pintype "bidirectional"))
      (node (ref "R156") (pin "1") (pinfunction "1_1") (pintype "passive"))
      (node (ref "R160") (pin "1") (pinfunction "1_1") (pintype "passive"))
    )
    (net (code "42") (name "/QSPI0_IO3") (class "Default")
      (node (ref "IC33") (pin "Y7") (pinfunction "D03_0_Y7") (pintype "bidirectional"))
      (node (ref "R159") (pin "1") (pinfunction "1_1") (pintype "passive"))
      (node (ref "R198") (pin "1") (pinfunction "1_1") (pintype "passive"))
    )
    (net (code "43") (name "/QSPI1_CS_B") (class "Default")
      (node (ref "IC3") (pin "7") (pinfunction "~{S}_7") (pintype "input"))
      (node (ref "R163") (pin "1") (pinfunction "1_1") (pintype "passive"))
    )
    (net (code "44") (name "/QSPI1_IO0") (class "Default")
      (node (ref "R199") (pin "1") (pinfunction "1_1") (pintype "passive"))
    )
    (net (code "45") (name "/QSPI1_IO1") (class "Default")
      (node (ref "R200") (pin "1") (pinfunction "1_1") (pintype "passive"))
    )
    (net (code "46") (name "/QSPI1_IO2") (class "Default")
      (node (ref "R170") (pin "1") (pinfunction "1_1") (pintype "passive"))
      (node (ref "R201") (pin "1") (pinfunction "1_1") (pintype "passive"))
    )
    (net (code "47") (name "/QSPI1_IO3") (class "Default")
      (node (ref "R162") (pin "1") (pinfunction "1_1") (pintype "passive"))
      (node (ref "R202") (pin "1") (pinfunction "1_1") (pintype "passive"))
    )
    (net (code "48") (name "/SYSMON_VN_R") (class "Default")
      (node (ref "C180") (pin "1") (pinfunction "1_1") (pintype "passive"))
      (node (ref "IC33") (pin "W11") (pinfunction "VN_W11") (pintype "input"))
    )
    (net (code "49") (name "/SYSMON_VP_R") (class "Default")
      (node (ref "C180") (pin "2") (pinfunction "2_2") (pintype "passive"))
      (node (ref "IC33") (pin "V12") (pinfunction "VP_V12") (pintype "input"))
    )
    (net (code "50") (name "/Vref64") (class "Default")
      (node (ref "C179") (pin "1") (pinfunction "1_1") (pintype "passive"))
      (node (ref "IC33") (pin "AD13") (pinfunction "VREF_64_AD13") (pintype "power_in"))
    )
    (net (code "52") (name "/Vref66") (class "Default")
      (node (ref "C102") (pin "1") (pinfunction "1_1") (pintype "passive"))
      (node (ref "IC33") (pin "L10") (pinfunction "VREF_66_L10") (pintype "power_in"))
    )
    (net (code "53") (name "/Vref67") (class "Default")
      (node (ref "C103") (pin "1") (pinfunction "1_1") (pintype "passive"))
      (node (ref "IC33") (pin "J20") (pinfunction "VREF_67_J20") (pintype "power_in"))
    )
    (net (code "59") (name "GND") (class "Default")
      (node (ref "C101") (pin "1") (pinfunction "1_1") (pintype "passive"))
      (node (ref "C102") (pin "2") (pinfunction "2_2") (pintype "passive"))
      (node (ref "C103") (pin "2") (pinfunction "2_2") (pintype "passive"))
      (node (ref "C168") (pin "1") (pinfunction "1_1") (pintype "passive"))
      (node (ref "C169") (pin "2") (pinfunction "2_2") (pintype "passive"))
      (node (ref "C170") (pin "2") (pinfunction "2_2") (pintype "passive"))
      (node (ref "C171") (pin "2") (pinfunction "2_2") (pintype "passive"))
      (node (ref "C172") (pin "2") (pinfunction "2_2") (pintype "passive"))
      (node (ref "C174") (pin "1") (pinfunction "1_1") (pintype "passive"))
      (node (ref "C175") (pin "2") (pinfunction "2_2") (pintype "passive"))
      (node (ref "C176") (pin "1") (pinfunction "1_1") (pintype "passive"))
      (node (ref "C177") (pin "2") (pinfunction "2_2") (pintype "passive"))
      (node (ref "C178") (pin "2") (pinfunction "2_2") (pintype "passive"))
      (node (ref "C179") (pin "2") (pinfunction "2_2") (pintype "passive"))
      (node (ref "IC2") (pin "10") (pinfunction "VSS_10") (pintype "power_in"))
      (node (ref "IC27") (pin "7") (pinfunction "GND_7") (pintype "power_in"))
      (node (ref "IC3") (pin "10") (pinfunction "VSS_10") (pintype "power_in"))
      (node (ref "IC33") (pin "V11") (pinfunction "VREFN_V11") (pintype "power_in"))
      (node (ref "R16") (pin "2") (pinfunction "2_2") (pintype "passive"))
      (node (ref "R166") (pin "1") (pinfunction "1_1") (pintype "passive"))
      (node (ref "R168") (pin "1") (pinfunction "1_1") (pintype "passive"))
      (node (ref "R171") (pin "1") (pinfunction "1_1") (pintype "passive"))
      (node (ref "R175") (pin "1") (pinfunction "1_1") (pintype "passive"))
      (node (ref "R177") (pin "1") (pinfunction "1_1") (pintype "passive"))
      (node (ref "R178") (pin "1") (pinfunction "1_1") (pintype "passive"))
      (node (ref "R185") (pin "1") (pinfunction "1_1") (pintype "passive"))
      (node (ref "R576") (pin "1") (pinfunction "1_1") (pintype "passive"))
      (node (ref "T17") (pin "2") (pinfunction "S_2") (pintype "passive"))
    )
    (net (code "60") (name "MGTAVTT") (class "Default")
      (node (ref "IC33") (pin "AP6") (pinfunction "MGTAVTTRCAL_R_AP6") (pintype "input"))
      (node (ref "R405") (pin "2") (pinfunction "2_2") (pintype "passive"))
    )
    (net (code "61") (name "Net-(C101-Pad2)") (class "Default")
      (node (ref "C101") (pin "2") (pinfunction "2_2") (pintype "passive"))
      (node (ref "R13") (pin "1") (pinfunction "1_1") (pintype "passive"))
    )
    (net (code "62") (name "Net-(IC2-DQ0)") (class "Default")
      (node (ref "IC2") (pin "15") (pinfunction "DQ0_15") (pintype "bidirectional"))
      (node (ref "R91") (pin "2") (pinfunction "2_2") (pintype "passive"))
    )
    (net (code "63") (name "Net-(IC2-DQ1)") (class "Default")
      (node (ref "IC2") (pin "8") (pinfunction "DQ1_8") (pintype "bidirectional"))
      (node (ref "R109") (pin "2") (pinfunction "2_2") (pintype "passive"))
    )
    (net (code "64") (name "Net-(IC2-~{HOLD}{slash}DQ3)") (class "Default")
      (node (ref "IC2") (pin "1") (pinfunction "~{HOLD}/DQ3_1") (pintype "bidirectional"))
      (node (ref "R198") (pin "2") (pinfunction "2_2") (pintype "passive"))
    )
    (net (code "65") (name "Net-(IC2-~{RESET})") (class "Default")
      (node (ref "IC2") (pin "3") (pinfunction "~{RESET}_3") (pintype "input"))
      (node (ref "R10") (pin "1") (pinfunction "1_1") (pintype "passive"))
    )
    (net (code "66") (name "Net-(IC2-~{W}{slash}DQ2)") (class "Default")
      (node (ref "IC2") (pin "9") (pinfunction "~{W}/DQ2_9") (pintype "bidirectional"))
      (node (ref "R156") (pin "2") (pinfunction "2_2") (pintype "passive"))
    )
    (net (code "67") (name "Net-(IC3-DQ0)") (class "Default")
      (node (ref "IC3") (pin "15") (pinfunction "DQ0_15") (pintype "bidirectional"))
      (node (ref "R199") (pin "2") (pinfunction "2_2") (pintype "passive"))
    )
    (net (code "68") (name "Net-(IC3-DQ1)") (class "Default")
      (node (ref "IC3") (pin "8") (pinfunction "DQ1_8") (pintype "bidirectional"))
      (node (ref "R200") (pin "2") (pinfunction "2_2") (pintype "passive"))
    )
    (net (code "69") (name "Net-(IC3-~{HOLD}{slash}DQ3)") (class "Default")
      (node (ref "IC3") (pin "1") (pinfunction "~{HOLD}/DQ3_1") (pintype "bidirectional"))
      (node (ref "R202") (pin "2") (pinfunction "2_2") (pintype "passive"))
    )
    (net (code "70") (name "Net-(IC3-~{RESET})") (class "Default")
      (node (ref "IC3") (pin "3") (pinfunction "~{RESET}_3") (pintype "input"))
      (node (ref "R12") (pin "1") (pinfunction "1_1") (pintype "passive"))
    )
    (net (code "71") (name "Net-(IC3-~{W}{slash}DQ2)") (class "Default")
      (node (ref "IC3") (pin "9") (pinfunction "~{W}/DQ2_9") (pintype "bidirectional"))
      (node (ref "R201") (pin "2") (pinfunction "2_2") (pintype "passive"))
    )
    (net (code "72") (name "Net-(IC33P-VREFP)") (class "Default")
      (node (ref "IC33") (pin "W12") (pinfunction "VREFP_W12") (pintype "power_in"))
      (node (ref "R16") (pin "1") (pinfunction "1_1") (pintype "passive"))
    )
    (net (code "73") (name "Net-(IC33P-VREF_65)") (class "Default")
      (node (ref "C178") (pin "1") (pinfunction "1_1") (pintype "passive"))
      (node (ref "IC33") (pin "J21") (pinfunction "VREF_65_J21") (pintype "power_in"))
    )
    (net (code "74") (name "Net-(LD3-C)") (class "Default")
      (node (ref "LD3") (pin "1") (pinfunction "C_1") (pintype "passive"))
      (node (ref "R245") (pin "1") (pinfunction "1_1") (pintype "passive"))
    )
    (net (code "75") (name "Net-(R175-Pad2)") (class "Default")
      (node (ref "R175") (pin "2") (pinfunction "2_2") (pintype "passive"))
      (node (ref "SW1") (pin "6") (pinfunction "6_6") (pintype "bidirectional"))
    )
    (net (code "76") (name "Net-(R177-Pad2)") (class "Default")
      (node (ref "R177") (pin "2") (pinfunction "2_2") (pintype "passive"))
      (node (ref "SW1") (pin "7") (pinfunction "7_7") (pintype "bidirectional"))
    )
    (net (code "77") (name "Net-(R178-Pad2)") (class "Default")
      (node (ref "R178") (pin "2") (pinfunction "2_2") (pintype "passive"))
      (node (ref "SW1") (pin "8") (pinfunction "8_8") (pintype "bidirectional"))
    )
    (net (code "78") (name "Net-(R185-Pad2)") (class "Default")
      (node (ref "R185") (pin "2") (pinfunction "2_2") (pintype "passive"))
      (node (ref "SW1") (pin "5") (pinfunction "5_5") (pintype "bidirectional"))
    )
    (net (code "79") (name "Net-(T17-D)") (class "Default")
      (node (ref "R245") (pin "2") (pinfunction "2_2") (pintype "passive"))
      (node (ref "T17") (pin "3") (pinfunction "D_3") (pintype "passive"))
    )
    (net (code "80") (name "P1V8") (class "Default")
      (node (ref "R575") (pin "1") (pinfunction "1_1") (pintype "passive"))
    )
    (net (code "81") (name "P3V3") (class "Default")
      (node (ref "C168") (pin "2") (pinfunction "2_2") (pintype "passive"))
      (node (ref "C174") (pin "2") (pinfunction "2_2") (pintype "passive"))
      (node (ref "IC2") (pin "2") (pinfunction "VCC_2") (pintype "power_in"))
      (node (ref "IC3") (pin "2") (pinfunction "VCC_2") (pintype "power_in"))
      (node (ref "IC33") (pin "W7") (pinfunction "CFGBVS_0_W7") (pintype "input"))
      (node (ref "LD3") (pin "2") (pinfunction "A_2") (pintype "passive"))
      (node (ref "R10") (pin "2") (pinfunction "2_2") (pintype "passive"))
      (node (ref "R12") (pin "2") (pinfunction "2_2") (pintype "passive"))
      (node (ref "R159") (pin "2") (pinfunction "2_2") (pintype "passive"))
      (node (ref "R160") (pin "2") (pinfunction "2_2") (pintype "passive"))
      (node (ref "R161") (pin "2") (pinfunction "2_2") (pintype "passive"))
      (node (ref "R162") (pin "2") (pinfunction "2_2") (pintype "passive"))
      (node (ref "R163") (pin "2") (pinfunction "2_2") (pintype "passive"))
      (node (ref "R164") (pin "2") (pinfunction "2_2") (pintype "passive"))
      (node (ref "R165") (pin "2") (pinfunction "2_2") (pintype "passive"))
      (node (ref "R167") (pin "2") (pinfunction "2_2") (pintype "passive"))
      (node (ref "R169") (pin "2") (pinfunction "2_2") (pintype "passive"))
      (node (ref "R170") (pin "2") (pinfunction "2_2") (pintype "passive"))
      (node (ref "R176") (pin "1") (pinfunction "1_1") (pintype "passive"))
      (node (ref "R179") (pin "1") (pinfunction "1_1") (pintype "passive"))
      (node (ref "R180") (pin "1") (pinfunction "1_1") (pintype "passive"))
      (node (ref "R184") (pin "1") (pinfunction "1_1") (pintype "passive"))
    )
    (net (code "82") (name "P3V3MP") (class "Default")
      (node (ref "C176") (pin "2") (pinfunction "2_2") (pintype "passive"))
      (node (ref "IC27") (pin "14") (pinfunction "VCC_14") (pintype "power_in"))
    )
    (net (code "83") (name "unconnected-(IC2-DNU-Pad4)") (class "Default")
      (node (ref "IC2") (pin "4") (pinfunction "DNU_4") (pintype "passive"))
    )
    (net (code "84") (name "unconnected-(IC2-DNU-Pad5)") (class "Default")
      (node (ref "IC2") (pin "5") (pinfunction "DNU_5") (pintype "passive"))
    )
    (net (code "85") (name "unconnected-(IC2-DNU-Pad6)") (class "Default")
      (node (ref "IC2") (pin "6") (pinfunction "DNU_6") (pintype "passive"))
    )
    (net (code "86") (name "unconnected-(IC2-DNU-Pad11)") (class "Default")
      (node (ref "IC2") (pin "11") (pinfunction "DNU_11") (pintype "passive"))
    )
    (net (code "87") (name "unconnected-(IC2-DNU-Pad12)") (class "Default")
      (node (ref "IC2") (pin "12") (pinfunction "DNU_12") (pintype "passive"))
    )
    (net (code "88") (name "unconnected-(IC2-DNU-Pad13)") (class "Default")
      (node (ref "IC2") (pin "13") (pinfunction "DNU_13") (pintype "passive"))
    )
    (net (code "89") (name "unconnected-(IC2-DNU-Pad14)") (class "Default")
      (node (ref "IC2") (pin "14") (pinfunction "DNU_14") (pintype "passive"))
    )
    (net (code "90") (name "unconnected-(IC3-DNU-Pad4)") (class "Default")
      (node (ref "IC3") (pin "4") (pinfunction "DNU_4") (pintype "passive"))
    )
    (net (code "91") (name "unconnected-(IC3-DNU-Pad5)") (class "Default")
      (node (ref "IC3") (pin "5") (pinfunction "DNU_5") (pintype "passive"))
    )
    (net (code "92") (name "unconnected-(IC3-DNU-Pad6)") (class "Default")
      (node (ref "IC3") (pin "6") (pinfunction "DNU_6") (pintype "passive"))
    )
    (net (code "93") (name "unconnected-(IC3-DNU-Pad11)") (class "Default")
      (node (ref "IC3") (pin "11") (pinfunction "DNU_11") (pintype "passive"))
    )
    (net (code "94") (name "unconnected-(IC3-DNU-Pad12)") (class "Default")
      (node (ref "IC3") (pin "12") (pinfunction "DNU_12") (pintype "passive"))
    )
    (net (code "95") (name "unconnected-(IC3-DNU-Pad13)") (class "Default")
      (node (ref "IC3") (pin "13") (pinfunction "DNU_13") (pintype "passive"))
    )
    (net (code "96") (name "unconnected-(IC3-DNU-Pad14)") (class "Default")
      (node (ref "IC3") (pin "14") (pinfunction "DNU_14") (pintype "passive"))
    )
  )
)
